# Battery.net
KiCad netlist of a schematic drawn in Altium Designer
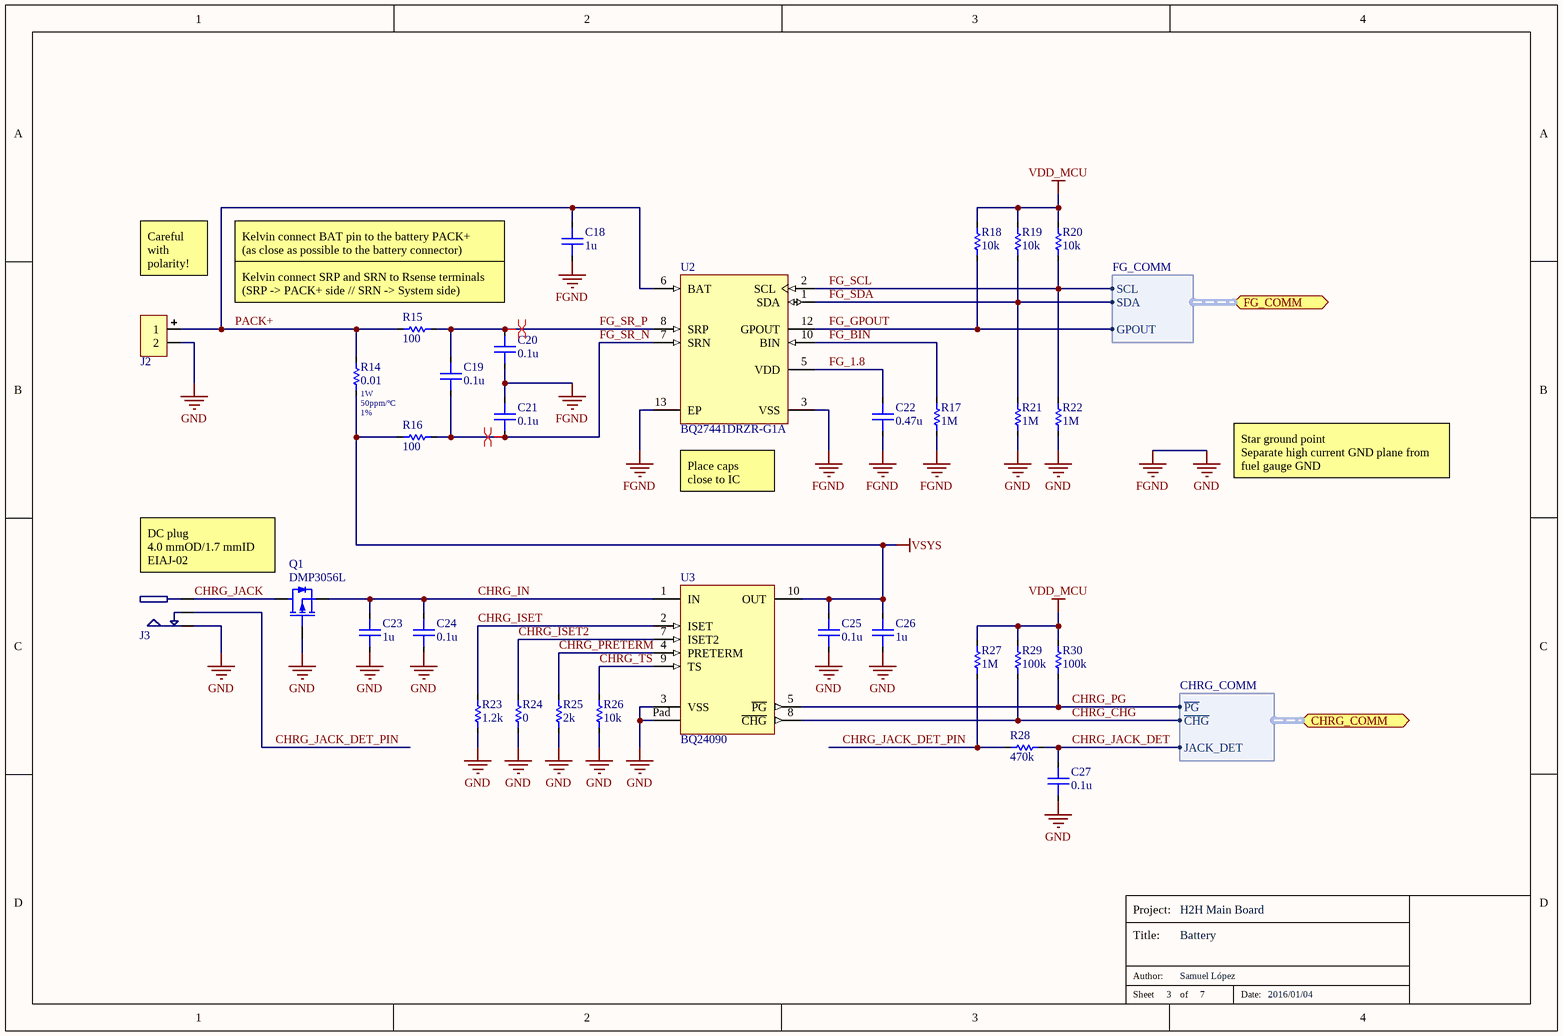
[diagram p0: Battery.SchDoc]

(export (version "E")
  (design (tool "Eeschema 10.0.6"))
  (components
    (comp (ref "C18")
      (value "1u")
      (footprint "C0603")
      (description "Capacitor")
      (libsource (lib "Misc") (part "Capacitor"))
    )
    (comp (ref "C19")
      (value "0.1u")
      (footprint "C0603")
      (description "Capacitor")
      (libsource (lib "Misc") (part "Capacitor"))
    )
    (comp (ref "C20")
      (value "0.1u")
      (footprint "C0603")
      (description "Capacitor")
      (libsource (lib "Misc") (part "Capacitor"))
    )
    (comp (ref "C21")
      (value "0.1u")
      (footprint "C0603")
      (description "Capacitor")
      (libsource (lib "Misc") (part "Capacitor"))
    )
    (comp (ref "C22")
      (value "0.47u")
      (footprint "C0603")
      (description "Capacitor")
      (libsource (lib "Misc") (part "Capacitor"))
    )
    (comp (ref "C23")
      (value "1u")
      (footprint "C0603")
      (description "Capacitor")
      (libsource (lib "Misc") (part "Capacitor"))
    )
    (comp (ref "C24")
      (value "0.1u")
      (footprint "C0603")
      (description "Capacitor")
      (libsource (lib "Misc") (part "Capacitor"))
    )
    (comp (ref "C25")
      (value "0.1u")
      (footprint "C0603")
      (description "Capacitor")
      (libsource (lib "Misc") (part "Capacitor"))
    )
    (comp (ref "C26")
      (value "1u")
      (footprint "C0603")
      (description "Capacitor")
      (libsource (lib "Misc") (part "Capacitor"))
    )
    (comp (ref "C27")
      (value "0.1u")
      (footprint "C0603")
      (description "Capacitor")
      (libsource (lib "Misc") (part "Capacitor"))
    )
    (comp (ref "J2")
      (value "JST PH 2 Pin")
      (footprint "S2B-PH-K-S")
      (description "Conn - Battery, Male, 2 Pin, PCB, Right Angle")
      (libsource (lib "Conn") (part "S2B-PH-K-S"))
    )
    (comp (ref "J3")
      (value "PJ-018H-SMT")
      (footprint "PJ-018H-SMT")
      (description "Conn - DC Power Plug - 4.0 mmOD / 1.7 mmID")
      (libsource (lib "Conn") (part "PJ-018H-SMT"))
    )
    (comp (ref "Q1")
      (value "DMP3056L")
      (footprint "DMP3056L")
      (description "Transistor - MOSFET, P-Channel, 30V, 4.3A")
      (libsource (lib "H2H") (part "DMP3056L"))
    )
    (comp (ref "R14")
      (value "0.01")
      (footprint "R1206")
      (description "Resistor")
      (fields
        (field (name "POWER") "1W")
        (field (name "TOLERANCE") "1%")
        (field (name "TEMP. COEF.") "50ppm/ºC")
      )
      (libsource (lib "Misc") (part "Resistor"))
    )
    (comp (ref "R15")
      (value "100")
      (footprint "R0603")
      (description "Resistor")
      (libsource (lib "Misc") (part "Resistor"))
    )
    (comp (ref "R16")
      (value "100")
      (footprint "R0603")
      (description "Resistor")
      (libsource (lib "Misc") (part "Resistor"))
    )
    (comp (ref "R17")
      (value "1M")
      (footprint "R0603")
      (description "Resistor")
      (libsource (lib "Misc") (part "Resistor"))
    )
    (comp (ref "R18")
      (value "10k")
      (footprint "R0603")
      (description "Resistor")
      (libsource (lib "Misc") (part "Resistor"))
    )
    (comp (ref "R19")
      (value "10k")
      (footprint "R0603")
      (description "Resistor")
      (libsource (lib "Misc") (part "Resistor"))
    )
    (comp (ref "R20")
      (value "10k")
      (footprint "R0603")
      (description "Resistor")
      (libsource (lib "Misc") (part "Resistor"))
    )
    (comp (ref "R21")
      (value "1M")
      (footprint "R0603")
      (description "Resistor")
      (libsource (lib "Misc") (part "Resistor"))
    )
    (comp (ref "R22")
      (value "1M")
      (footprint "R0603")
      (description "Resistor")
      (libsource (lib "Misc") (part "Resistor"))
    )
    (comp (ref "R23")
      (value "1.2k")
      (footprint "R0603")
      (description "Resistor")
      (libsource (lib "Misc") (part "Resistor"))
    )
    (comp (ref "R24")
      (value "0")
      (footprint "R0603")
      (description "Resistor")
      (libsource (lib "Misc") (part "Resistor"))
    )
    (comp (ref "R25")
      (value "2k")
      (footprint "R0603")
      (description "Resistor")
      (libsource (lib "Misc") (part "Resistor"))
    )
    (comp (ref "R26")
      (value "10k")
      (footprint "R0603")
      (description "Resistor")
      (libsource (lib "Misc") (part "Resistor"))
    )
    (comp (ref "R27")
      (value "1M")
      (footprint "R0603")
      (description "Resistor")
      (libsource (lib "Misc") (part "Resistor"))
    )
    (comp (ref "R28")
      (value "470k")
      (footprint "R0603")
      (description "Resistor")
      (libsource (lib "Misc") (part "Resistor"))
    )
    (comp (ref "R29")
      (value "100k")
      (footprint "R0603")
      (description "Resistor")
      (libsource (lib "Misc") (part "Resistor"))
    )
    (comp (ref "R30")
      (value "100k")
      (footprint "R0603")
      (description "Resistor")
      (libsource (lib "Misc") (part "Resistor"))
    )
    (comp (ref "U2")
      (value "BQ27441DRZR-G1A")
      (footprint "BQ27441DRZx-G1A")
      (description "IC - Fuel Gauge, System-Side Impedance Track")
      (fields (field (name "PARTNUMBER") "BQ27410DRZR-G1A") (field (name "MANUFACTURER") "Texas Instruments"))
      (libsource (lib "H2H") (part "BQ27441DRZR-G1A"))
    )
    (comp (ref "U3")
      (value "BQ24090")
      (footprint "BQ24090")
      (description "IC - Battery Charger, Single Cell Li-Ion/LiPo, 1A")
      (libsource (lib "H2H") (part "BQ24090"))
    )
  )
  (nets
    (net (code "3") (name "/CHRG_CHG") (class "Default")
      (node (ref "R29") (pin "2") (pinfunction "2_2") (pintype "passive"))
      (node (ref "U3") (pin "8") (pinfunction "~{CHG}_8") (pintype "output"))
    )
    (net (code "4") (name "/CHRG_IN") (class "Default")
      (node (ref "C23") (pin "2") (pinfunction "2_2") (pintype "passive"))
      (node (ref "C24") (pin "2") (pinfunction "2_2") (pintype "passive"))
      (node (ref "Q1") (pin "2") (pinfunction "S_2") (pintype "passive"))
      (node (ref "U3") (pin "1") (pinfunction "IN_1") (pintype "power_in"))
    )
    (net (code "5") (name "/CHRG_ISET") (class "Default")
      (node (ref "R23") (pin "1") (pinfunction "1_1") (pintype "passive"))
      (node (ref "U3") (pin "2") (pinfunction "ISET_2") (pintype "input"))
    )
    (net (code "6") (name "/CHRG_ISET2") (class "Default")
      (node (ref "R24") (pin "1") (pinfunction "1_1") (pintype "passive"))
      (node (ref "U3") (pin "7") (pinfunction "ISET2_7") (pintype "input"))
    )
    (net (code "7") (name "/CHRG_JACK") (class "Default")
      (node (ref "J3") (pin "1") (pinfunction "1_1") (pintype "passive"))
      (node (ref "Q1") (pin "3") (pinfunction "D_3") (pintype "passive"))
    )
    (net (code "8") (name "/CHRG_JACK_DET") (class "Default")
      (node (ref "C27") (pin "2") (pinfunction "2_2") (pintype "passive"))
      (node (ref "R28") (pin "1") (pinfunction "1_1") (pintype "passive"))
    )
    (net (code "9") (name "/CHRG_JACK_DET_PIN") (class "Default")
      (node (ref "J3") (pin "3") (pinfunction "3_3") (pintype "passive"))
      (node (ref "R27") (pin "2") (pinfunction "2_2") (pintype "passive"))
      (node (ref "R28") (pin "2") (pinfunction "2_2") (pintype "passive"))
    )
    (net (code "10") (name "/CHRG_PG") (class "Default")
      (node (ref "R30") (pin "2") (pinfunction "2_2") (pintype "passive"))
      (node (ref "U3") (pin "5") (pinfunction "~{PG}_5") (pintype "output"))
    )
    (net (code "11") (name "/CHRG_PRETERM") (class "Default")
      (node (ref "R25") (pin "1") (pinfunction "1_1") (pintype "passive"))
      (node (ref "U3") (pin "4") (pinfunction "PRETERM_4") (pintype "input"))
    )
    (net (code "12") (name "/CHRG_TS") (class "Default")
      (node (ref "R26") (pin "1") (pinfunction "1_1") (pintype "passive"))
      (node (ref "U3") (pin "9") (pinfunction "TS_9") (pintype "input"))
    )
    (net (code "13") (name "/FG_1.8") (class "Default")
      (node (ref "C22") (pin "2") (pinfunction "2_2") (pintype "passive"))
      (node (ref "U2") (pin "5") (pinfunction "VDD_5") (pintype "power_in"))
    )
    (net (code "14") (name "/FG_BIN") (class "Default")
      (node (ref "R17") (pin "1") (pinfunction "1_1") (pintype "passive"))
      (node (ref "U2") (pin "10") (pinfunction "BIN_10") (pintype "input"))
    )
    (net (code "15") (name "/FG_GPOUT") (class "Default")
      (node (ref "R18") (pin "2") (pinfunction "2_2") (pintype "passive"))
      (node (ref "U2") (pin "12") (pinfunction "GPOUT_12") (pintype "open_collector"))
    )
    (net (code "16") (name "/FG_SCL") (class "Default")
      (node (ref "R20") (pin "2") (pinfunction "2_2") (pintype "passive"))
      (node (ref "R22") (pin "1") (pinfunction "1_1") (pintype "passive"))
      (node (ref "U2") (pin "2") (pinfunction "SCL_2") (pintype "input"))
    )
    (net (code "17") (name "/FG_SDA") (class "Default")
      (node (ref "R19") (pin "2") (pinfunction "2_2") (pintype "passive"))
      (node (ref "R21") (pin "1") (pinfunction "1_1") (pintype "passive"))
      (node (ref "U2") (pin "1") (pinfunction "SDA_1") (pintype "bidirectional"))
    )
    (net (code "18") (name "/FG_SR_N") (class "Default")
      (node (ref "C19") (pin "1") (pinfunction "1_1") (pintype "passive"))
      (node (ref "C21") (pin "1") (pinfunction "1_1") (pintype "passive"))
      (node (ref "R16") (pin "2") (pinfunction "2_2") (pintype "passive"))
      (node (ref "U2") (pin "7") (pinfunction "SRN_7") (pintype "input"))
    )
    (net (code "19") (name "/FG_SR_P") (class "Default")
      (node (ref "C19") (pin "2") (pinfunction "2_2") (pintype "passive"))
      (node (ref "C20") (pin "2") (pinfunction "2_2") (pintype "passive"))
      (node (ref "R15") (pin "2") (pinfunction "2_2") (pintype "passive"))
      (node (ref "U2") (pin "8") (pinfunction "SRP_8") (pintype "input"))
    )
    (net (code "20") (name "/PACK+") (class "Default")
      (node (ref "C18") (pin "2") (pinfunction "2_2") (pintype "passive"))
      (node (ref "J2") (pin "1") (pinfunction "1_1") (pintype "passive"))
      (node (ref "R14") (pin "1") (pinfunction "1_1") (pintype "passive"))
      (node (ref "R15") (pin "1") (pinfunction "1_1") (pintype "passive"))
      (node (ref "U2") (pin "6") (pinfunction "BAT_6") (pintype "input"))
    )
    (net (code "23") (name "FGND") (class "Default")
      (node (ref "C18") (pin "1") (pinfunction "1_1") (pintype "passive"))
      (node (ref "C20") (pin "1") (pinfunction "1_1") (pintype "passive"))
      (node (ref "C21") (pin "2") (pinfunction "2_2") (pintype "passive"))
      (node (ref "C22") (pin "1") (pinfunction "1_1") (pintype "passive"))
      (node (ref "C23") (pin "1") (pinfunction "1_1") (pintype "passive"))
      (node (ref "C24") (pin "1") (pinfunction "1_1") (pintype "passive"))
      (node (ref "C25") (pin "1") (pinfunction "1_1") (pintype "passive"))
      (node (ref "C26") (pin "1") (pinfunction "1_1") (pintype "passive"))
      (node (ref "C27") (pin "1") (pinfunction "1_1") (pintype "passive"))
      (node (ref "J2") (pin "2") (pinfunction "2_2") (pintype "passive"))
      (node (ref "J3") (pin "2") (pinfunction "2_2") (pintype "passive"))
      (node (ref "Q1") (pin "1") (pinfunction "G_1") (pintype "passive"))
      (node (ref "R17") (pin "2") (pinfunction "2_2") (pintype "passive"))
      (node (ref "R21") (pin "2") (pinfunction "2_2") (pintype "passive"))
      (node (ref "R22") (pin "2") (pinfunction "2_2") (pintype "passive"))
      (node (ref "R23") (pin "2") (pinfunction "2_2") (pintype "passive"))
      (node (ref "R24") (pin "2") (pinfunction "2_2") (pintype "passive"))
      (node (ref "R25") (pin "2") (pinfunction "2_2") (pintype "passive"))
      (node (ref "R26") (pin "2") (pinfunction "2_2") (pintype "passive"))
      (node (ref "U2") (pin "13") (pinfunction "EP_13") (pintype "passive"))
      (node (ref "U2") (pin "3") (pinfunction "VSS_3") (pintype "power_in"))
      (node (ref "U3") (pin "3") (pinfunction "VSS_3") (pintype "power_in"))
      (node (ref "U3") (pin "Pad") (pinfunction "Thermal_Pad") (pintype "passive"))
    )
    (net (code "24") (name "VDD_MCU") (class "Default")
      (node (ref "R18") (pin "1") (pinfunction "1_1") (pintype "passive"))
      (node (ref "R19") (pin "1") (pinfunction "1_1") (pintype "passive"))
      (node (ref "R20") (pin "1") (pinfunction "1_1") (pintype "passive"))
      (node (ref "R27") (pin "1") (pinfunction "1_1") (pintype "passive"))
      (node (ref "R29") (pin "1") (pinfunction "1_1") (pintype "passive"))
      (node (ref "R30") (pin "1") (pinfunction "1_1") (pintype "passive"))
    )
    (net (code "25") (name "VSYS") (class "Default")
      (node (ref "C25") (pin "2") (pinfunction "2_2") (pintype "passive"))
      (node (ref "C26") (pin "2") (pinfunction "2_2") (pintype "passive"))
      (node (ref "R14") (pin "2") (pinfunction "2_2") (pintype "passive"))
      (node (ref "R16") (pin "1") (pinfunction "1_1") (pintype "passive"))
      (node (ref "U3") (pin "10") (pinfunction "OUT_10") (pintype "power_in"))
    )
  )
)
